# AP_AT42QT2120.net
KiCad netlist of a schematic drawn in EAGLE
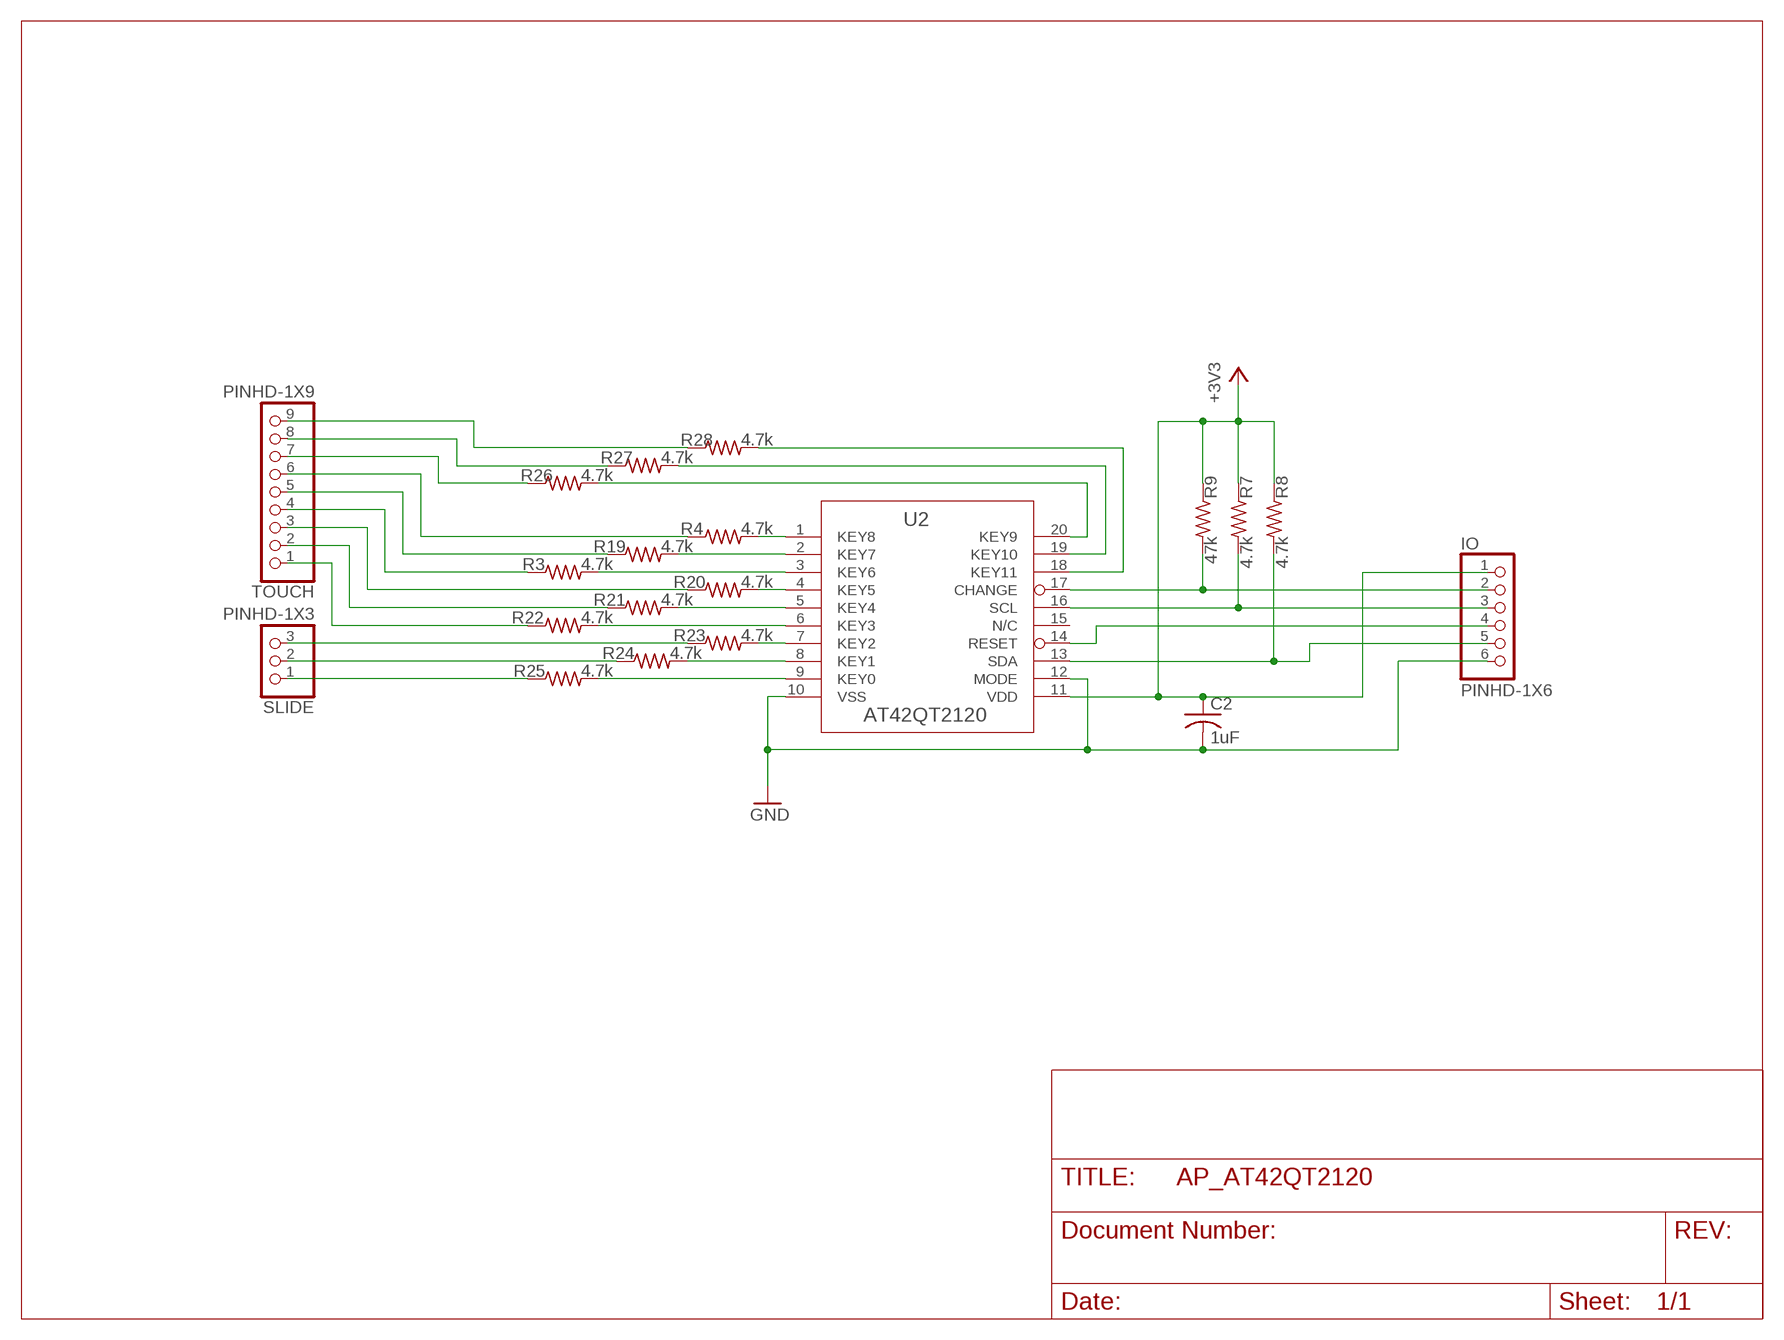
[diagram p0: schematic, sheet 1]

(export (version "E")
  (design (tool "Eeschema 10.0.6"))
  (components
    (comp (ref "C2")
      (value "1uF")
      (footprint "eagle-import:C0805")
      (libsource (lib "eagle-import") (part "C-USC0805"))
    )
    (comp (ref "IO")
      (value "PINHD-1X6")
      (footprint "eagle-import:1X06")
      (libsource (lib "eagle-import") (part "PINHD-1X6"))
    )
    (comp (ref "R3")
      (value "4.7k")
      (footprint "eagle-import:R0805")
      (libsource (lib "eagle-import") (part "R-US_R0805"))
    )
    (comp (ref "R4")
      (value "4.7k")
      (footprint "eagle-import:R0805")
      (libsource (lib "eagle-import") (part "R-US_R0805"))
    )
    (comp (ref "R7")
      (value "4.7k")
      (footprint "eagle-import:R0805")
      (libsource (lib "eagle-import") (part "R-US_R0805"))
    )
    (comp (ref "R8")
      (value "4.7k")
      (footprint "eagle-import:R0805")
      (libsource (lib "eagle-import") (part "R-US_R0805"))
    )
    (comp (ref "R9")
      (value "47k")
      (footprint "eagle-import:R0805")
      (libsource (lib "eagle-import") (part "R-US_R0805"))
    )
    (comp (ref "R19")
      (value "4.7k")
      (footprint "eagle-import:R0805")
      (libsource (lib "eagle-import") (part "R-US_R0805"))
    )
    (comp (ref "R20")
      (value "4.7k")
      (footprint "eagle-import:R0805")
      (libsource (lib "eagle-import") (part "R-US_R0805"))
    )
    (comp (ref "R21")
      (value "4.7k")
      (footprint "eagle-import:R0805")
      (libsource (lib "eagle-import") (part "R-US_R0805"))
    )
    (comp (ref "R22")
      (value "4.7k")
      (footprint "eagle-import:R0805")
      (libsource (lib "eagle-import") (part "R-US_R0805"))
    )
    (comp (ref "R23")
      (value "4.7k")
      (footprint "eagle-import:R0805")
      (libsource (lib "eagle-import") (part "R-US_R0805"))
    )
    (comp (ref "R24")
      (value "4.7k")
      (footprint "eagle-import:R0805")
      (libsource (lib "eagle-import") (part "R-US_R0805"))
    )
    (comp (ref "R25")
      (value "4.7k")
      (footprint "eagle-import:R0805")
      (libsource (lib "eagle-import") (part "R-US_R0805"))
    )
    (comp (ref "R26")
      (value "4.7k")
      (footprint "eagle-import:R0805")
      (libsource (lib "eagle-import") (part "R-US_R0805"))
    )
    (comp (ref "R27")
      (value "4.7k")
      (footprint "eagle-import:R0805")
      (libsource (lib "eagle-import") (part "R-US_R0805"))
    )
    (comp (ref "R28")
      (value "4.7k")
      (footprint "eagle-import:R1206")
      (libsource (lib "eagle-import") (part "R-US_R1206"))
    )
    (comp (ref "SLIDE")
      (value "PINHD-1X3")
      (footprint "eagle-import:1X03")
      (libsource (lib "eagle-import") (part "PINHD-1X3"))
    )
    (comp (ref "TOUCH")
      (value "PINHD-1X9")
      (footprint "eagle-import:1X09")
      (libsource (lib "eagle-import") (part "PINHD-1X9"))
    )
    (comp (ref "U2")
      (value "AT42QT2120")
      (footprint "eagle-import:TSSOP20_MC_MCH-L")
      (fields
        (field (name "MANUFACTURER_PART_NUMBER") "AT42QT2120-XU")
        (field (name "COPYRIGHT") "Copyright (C) 2022 Ultra Librarian. All rights reserved.")
      )
      (libsource (lib "eagle-import") (part "AT42QT2120-XUTSSOP20_MC_MCH-L"))
    )
  )
  (nets
    (net (code "1") (name "+3V3") (class "Default")
      (node (ref "C2") (pin "1") (pinfunction "1_1") (pintype "passive"))
      (node (ref "IO") (pin "1") (pinfunction "1_1") (pintype "passive"))
      (node (ref "R7") (pin "1") (pinfunction "1_1") (pintype "passive"))
      (node (ref "R8") (pin "1") (pinfunction "1_1") (pintype "passive"))
      (node (ref "R9") (pin "1") (pinfunction "1_1") (pintype "passive"))
      (node (ref "U2") (pin "11") (pinfunction "VDD_11") (pintype "power_in"))
    )
    (net (code "2") (name "GND") (class "Default")
      (node (ref "C2") (pin "2") (pinfunction "2_2") (pintype "passive"))
      (node (ref "IO") (pin "6") (pinfunction "6_6") (pintype "passive"))
      (node (ref "U2") (pin "10") (pinfunction "VSS_10") (pintype "passive"))
      (node (ref "U2") (pin "12") (pinfunction "MODE_12") (pintype "passive"))
    )
    (net (code "3") (name "Net-(R3-Pad1)") (class "Default")
      (node (ref "R3") (pin "1") (pinfunction "1_1") (pintype "passive"))
      (node (ref "TOUCH") (pin "4") (pinfunction "4_4") (pintype "passive"))
    )
    (net (code "4") (name "Net-(R4-Pad1)") (class "Default")
      (node (ref "R4") (pin "1") (pinfunction "1_1") (pintype "passive"))
      (node (ref "TOUCH") (pin "6") (pinfunction "6_6") (pintype "passive"))
    )
    (net (code "5") (name "Net-(R19-Pad1)") (class "Default")
      (node (ref "R19") (pin "1") (pinfunction "1_1") (pintype "passive"))
      (node (ref "TOUCH") (pin "5") (pinfunction "5_5") (pintype "passive"))
    )
    (net (code "6") (name "Net-(R20-Pad1)") (class "Default")
      (node (ref "R20") (pin "1") (pinfunction "1_1") (pintype "passive"))
      (node (ref "TOUCH") (pin "3") (pinfunction "3_3") (pintype "passive"))
    )
    (net (code "7") (name "Net-(R21-Pad1)") (class "Default")
      (node (ref "R21") (pin "1") (pinfunction "1_1") (pintype "passive"))
      (node (ref "TOUCH") (pin "2") (pinfunction "2_2") (pintype "passive"))
    )
    (net (code "8") (name "Net-(R22-Pad1)") (class "Default")
      (node (ref "R22") (pin "1") (pinfunction "1_1") (pintype "passive"))
      (node (ref "TOUCH") (pin "1") (pinfunction "1_1") (pintype "passive"))
    )
    (net (code "9") (name "Net-(R23-Pad1)") (class "Default")
      (node (ref "R23") (pin "1") (pinfunction "1_1") (pintype "passive"))
      (node (ref "SLIDE") (pin "3") (pinfunction "3_3") (pintype "passive"))
    )
    (net (code "10") (name "Net-(R24-Pad1)") (class "Default")
      (node (ref "R24") (pin "1") (pinfunction "1_1") (pintype "passive"))
      (node (ref "SLIDE") (pin "2") (pinfunction "2_2") (pintype "passive"))
    )
    (net (code "11") (name "Net-(R25-Pad1)") (class "Default")
      (node (ref "R25") (pin "1") (pinfunction "1_1") (pintype "passive"))
      (node (ref "SLIDE") (pin "1") (pinfunction "1_1") (pintype "passive"))
    )
    (net (code "12") (name "Net-(R26-Pad1)") (class "Default")
      (node (ref "R26") (pin "1") (pinfunction "1_1") (pintype "passive"))
      (node (ref "TOUCH") (pin "7") (pinfunction "7_7") (pintype "passive"))
    )
    (net (code "13") (name "Net-(R27-Pad1)") (class "Default")
      (node (ref "R27") (pin "1") (pinfunction "1_1") (pintype "passive"))
      (node (ref "TOUCH") (pin "8") (pinfunction "8_8") (pintype "passive"))
    )
    (net (code "14") (name "Net-(R28-Pad1)") (class "Default")
      (node (ref "R28") (pin "1") (pinfunction "1_1") (pintype "passive"))
      (node (ref "TOUCH") (pin "9") (pinfunction "9_9") (pintype "passive"))
    )
    (net (code "15") (name "Net-(U2-CHANGE)") (class "Default")
      (node (ref "IO") (pin "2") (pinfunction "2_2") (pintype "passive"))
      (node (ref "R9") (pin "2") (pinfunction "2_2") (pintype "passive"))
      (node (ref "U2") (pin "17") (pinfunction "CHANGE_17") (pintype "input"))
    )
    (net (code "16") (name "Net-(U2-KEY0)") (class "Default")
      (node (ref "R25") (pin "2") (pinfunction "2_2") (pintype "passive"))
      (node (ref "U2") (pin "9") (pinfunction "KEY0_9") (pintype "bidirectional"))
    )
    (net (code "17") (name "Net-(U2-KEY1)") (class "Default")
      (node (ref "R24") (pin "2") (pinfunction "2_2") (pintype "passive"))
      (node (ref "U2") (pin "8") (pinfunction "KEY1_8") (pintype "bidirectional"))
    )
    (net (code "18") (name "Net-(U2-KEY2)") (class "Default")
      (node (ref "R23") (pin "2") (pinfunction "2_2") (pintype "passive"))
      (node (ref "U2") (pin "7") (pinfunction "KEY2_7") (pintype "bidirectional"))
    )
    (net (code "19") (name "Net-(U2-KEY3)") (class "Default")
      (node (ref "R22") (pin "2") (pinfunction "2_2") (pintype "passive"))
      (node (ref "U2") (pin "6") (pinfunction "KEY3_6") (pintype "bidirectional"))
    )
    (net (code "20") (name "Net-(U2-KEY4)") (class "Default")
      (node (ref "R21") (pin "2") (pinfunction "2_2") (pintype "passive"))
      (node (ref "U2") (pin "5") (pinfunction "KEY4_5") (pintype "bidirectional"))
    )
    (net (code "21") (name "Net-(U2-KEY5)") (class "Default")
      (node (ref "R20") (pin "2") (pinfunction "2_2") (pintype "passive"))
      (node (ref "U2") (pin "4") (pinfunction "KEY5_4") (pintype "bidirectional"))
    )
    (net (code "22") (name "Net-(U2-KEY6)") (class "Default")
      (node (ref "R3") (pin "2") (pinfunction "2_2") (pintype "passive"))
      (node (ref "U2") (pin "3") (pinfunction "KEY6_3") (pintype "bidirectional"))
    )
    (net (code "23") (name "Net-(U2-KEY7)") (class "Default")
      (node (ref "R19") (pin "2") (pinfunction "2_2") (pintype "passive"))
      (node (ref "U2") (pin "2") (pinfunction "KEY7_2") (pintype "bidirectional"))
    )
    (net (code "24") (name "Net-(U2-KEY8)") (class "Default")
      (node (ref "R4") (pin "2") (pinfunction "2_2") (pintype "passive"))
      (node (ref "U2") (pin "1") (pinfunction "KEY8_1") (pintype "bidirectional"))
    )
    (net (code "25") (name "Net-(U2-KEY9)") (class "Default")
      (node (ref "R26") (pin "2") (pinfunction "2_2") (pintype "passive"))
      (node (ref "U2") (pin "20") (pinfunction "KEY9_20") (pintype "bidirectional"))
    )
    (net (code "26") (name "Net-(U2-KEY10)") (class "Default")
      (node (ref "R27") (pin "2") (pinfunction "2_2") (pintype "passive"))
      (node (ref "U2") (pin "19") (pinfunction "KEY10_19") (pintype "bidirectional"))
    )
    (net (code "27") (name "Net-(U2-KEY11)") (class "Default")
      (node (ref "R28") (pin "2") (pinfunction "2_2") (pintype "passive"))
      (node (ref "U2") (pin "18") (pinfunction "KEY11_18") (pintype "bidirectional"))
    )
    (net (code "28") (name "Net-(U2-RESET)") (class "Default")
      (node (ref "IO") (pin "4") (pinfunction "4_4") (pintype "passive"))
      (node (ref "U2") (pin "14") (pinfunction "RESET_14") (pintype "passive"))
    )
    (net (code "29") (name "Net-(U2-SCL)") (class "Default")
      (node (ref "IO") (pin "3") (pinfunction "3_3") (pintype "passive"))
      (node (ref "R7") (pin "2") (pinfunction "2_2") (pintype "passive"))
      (node (ref "U2") (pin "16") (pinfunction "SCL_16") (pintype "bidirectional"))
    )
    (net (code "30") (name "Net-(U2-SDA)") (class "Default")
      (node (ref "IO") (pin "5") (pinfunction "5_5") (pintype "passive"))
      (node (ref "R8") (pin "2") (pinfunction "2_2") (pintype "passive"))
      (node (ref "U2") (pin "13") (pinfunction "SDA_13") (pintype "bidirectional"))
    )
    (net (code "31") (name "unconnected-(U2-N{slash}C-Pad15)") (class "Default")
      (node (ref "U2") (pin "15") (pinfunction "N/C_15") (pintype "no_connect"))
    )
  )
)
